# stm32l052k8t_dip.net
KiCad netlist of a schematic drawn in EAGLE
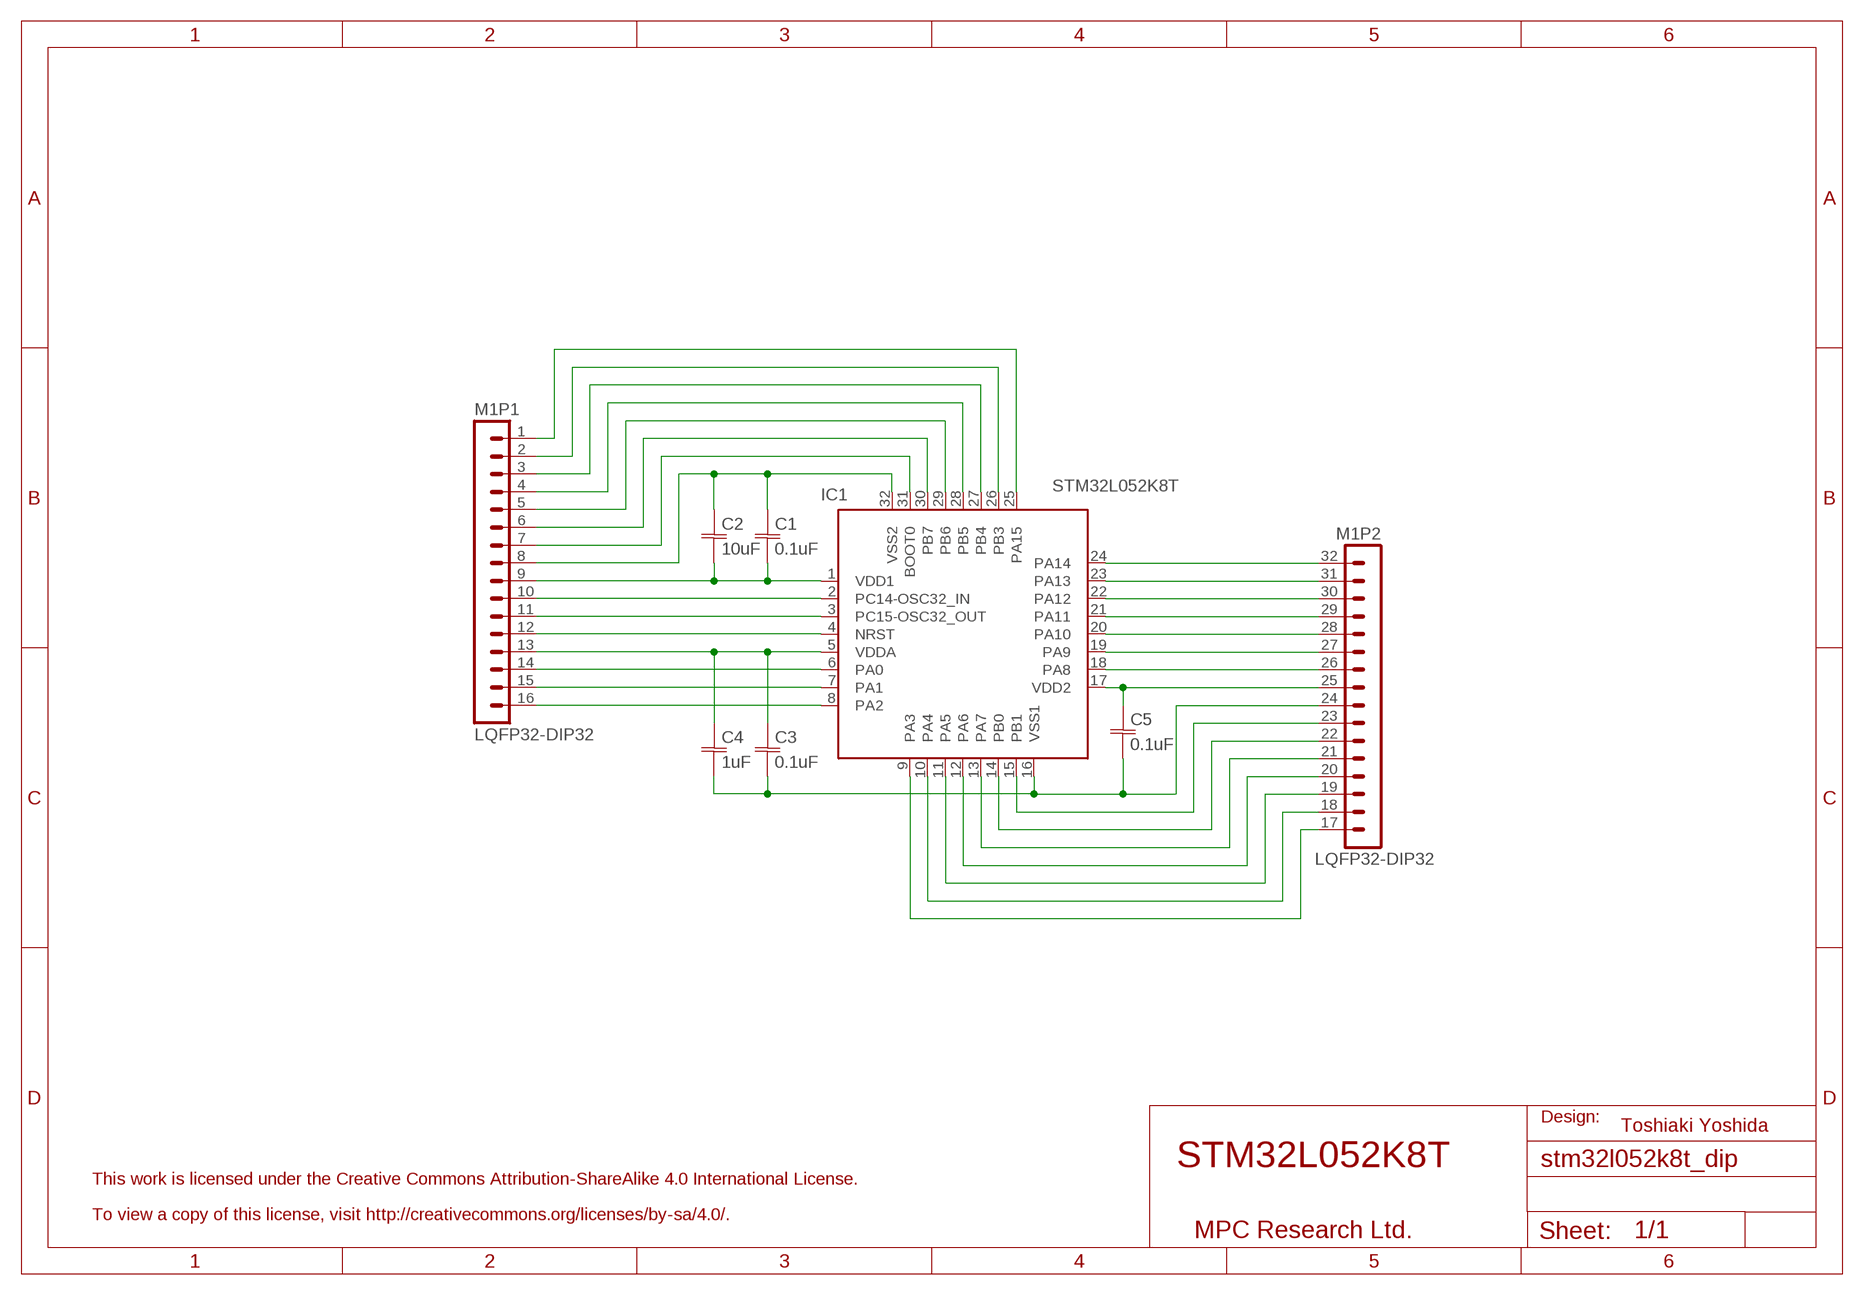
[diagram p0: schematic, sheet 1]

(export (version "E")
  (design (tool "Eeschema 10.0.6"))
  (components
    (comp (ref "C1")
      (value "0.1uF")
      (footprint "eagle-import:C0603")
      (libsource (lib "eagle-import") (part "C-JIS0603"))
    )
    (comp (ref "C2")
      (value "10uF")
      (footprint "eagle-import:C0603")
      (libsource (lib "eagle-import") (part "C-JIS0603"))
    )
    (comp (ref "C3")
      (value "0.1uF")
      (footprint "eagle-import:C0603")
      (libsource (lib "eagle-import") (part "C-JIS0603"))
    )
    (comp (ref "C4")
      (value "1uF")
      (footprint "eagle-import:C0603")
      (libsource (lib "eagle-import") (part "C-JIS0603"))
    )
    (comp (ref "C5")
      (value "0.1uF")
      (footprint "eagle-import:C0603")
      (libsource (lib "eagle-import") (part "C-JIS0603"))
    )
    (comp (ref "IC1")
      (value "STM32L052K8T")
      (footprint "eagle-import:LQFP-32")
      (libsource (lib "eagle-import") (part "STM32L052KT8"))
    )
    (comp (ref "M1")
      (value "LQFP32-DIP32")
      (footprint "eagle-import:LQFP32-DIP32")
      (libsource (lib "eagle-import") (part "LQFP32-DIP32"))
    )
  )
  (nets
    (net (code "1") (name "Net-(IC1-BOOT0)") (class "Default")
      (node (ref "IC1") (pin "31") (pinfunction "BOOT0_31") (pintype "input"))
      (node (ref "M1") (pin "7") (pinfunction "P7_7") (pintype "passive"))
    )
    (net (code "2") (name "Net-(IC1-NRST)") (class "Default")
      (node (ref "IC1") (pin "4") (pinfunction "NRST_4") (pintype "bidirectional"))
      (node (ref "M1") (pin "12") (pinfunction "P12_12") (pintype "passive"))
    )
    (net (code "3") (name "Net-(IC1-PA0)") (class "Default")
      (node (ref "IC1") (pin "6") (pinfunction "PA0_6") (pintype "bidirectional"))
      (node (ref "M1") (pin "14") (pinfunction "P14_14") (pintype "passive"))
    )
    (net (code "4") (name "Net-(IC1-PA1)") (class "Default")
      (node (ref "IC1") (pin "7") (pinfunction "PA1_7") (pintype "bidirectional"))
      (node (ref "M1") (pin "15") (pinfunction "P15_15") (pintype "passive"))
    )
    (net (code "5") (name "Net-(IC1-PA2)") (class "Default")
      (node (ref "IC1") (pin "8") (pinfunction "PA2_8") (pintype "bidirectional"))
      (node (ref "M1") (pin "16") (pinfunction "P16_16") (pintype "passive"))
    )
    (net (code "6") (name "Net-(IC1-PA3)") (class "Default")
      (node (ref "IC1") (pin "9") (pinfunction "PA3_9") (pintype "bidirectional"))
      (node (ref "M1") (pin "17") (pinfunction "P16_17") (pintype "passive"))
    )
    (net (code "7") (name "Net-(IC1-PA4)") (class "Default")
      (node (ref "IC1") (pin "10") (pinfunction "PA4_10") (pintype "bidirectional"))
      (node (ref "M1") (pin "18") (pinfunction "P15_18") (pintype "passive"))
    )
    (net (code "8") (name "Net-(IC1-PA5)") (class "Default")
      (node (ref "IC1") (pin "11") (pinfunction "PA5_11") (pintype "bidirectional"))
      (node (ref "M1") (pin "19") (pinfunction "P14_19") (pintype "passive"))
    )
    (net (code "9") (name "Net-(IC1-PA6)") (class "Default")
      (node (ref "IC1") (pin "12") (pinfunction "PA6_12") (pintype "bidirectional"))
      (node (ref "M1") (pin "20") (pinfunction "P13_20") (pintype "passive"))
    )
    (net (code "10") (name "Net-(IC1-PA7)") (class "Default")
      (node (ref "IC1") (pin "13") (pinfunction "PA7_13") (pintype "bidirectional"))
      (node (ref "M1") (pin "21") (pinfunction "P12_21") (pintype "passive"))
    )
    (net (code "11") (name "Net-(IC1-PA8)") (class "Default")
      (node (ref "IC1") (pin "18") (pinfunction "PA8_18") (pintype "bidirectional"))
      (node (ref "M1") (pin "26") (pinfunction "P7_26") (pintype "passive"))
    )
    (net (code "12") (name "Net-(IC1-PA9)") (class "Default")
      (node (ref "IC1") (pin "19") (pinfunction "PA9_19") (pintype "bidirectional"))
      (node (ref "M1") (pin "27") (pinfunction "P6_27") (pintype "passive"))
    )
    (net (code "13") (name "Net-(IC1-PA10)") (class "Default")
      (node (ref "IC1") (pin "20") (pinfunction "PA10_20") (pintype "bidirectional"))
      (node (ref "M1") (pin "28") (pinfunction "P5_28") (pintype "passive"))
    )
    (net (code "14") (name "Net-(IC1-PA11)") (class "Default")
      (node (ref "IC1") (pin "21") (pinfunction "PA11_21") (pintype "bidirectional"))
      (node (ref "M1") (pin "29") (pinfunction "P4_29") (pintype "passive"))
    )
    (net (code "15") (name "Net-(IC1-PA12)") (class "Default")
      (node (ref "IC1") (pin "22") (pinfunction "PA12_22") (pintype "bidirectional"))
      (node (ref "M1") (pin "30") (pinfunction "P3_30") (pintype "passive"))
    )
    (net (code "16") (name "Net-(IC1-PA13)") (class "Default")
      (node (ref "IC1") (pin "23") (pinfunction "PA13_23") (pintype "bidirectional"))
      (node (ref "M1") (pin "31") (pinfunction "P2_31") (pintype "passive"))
    )
    (net (code "17") (name "Net-(IC1-PA14)") (class "Default")
      (node (ref "IC1") (pin "24") (pinfunction "PA14_24") (pintype "bidirectional"))
      (node (ref "M1") (pin "32") (pinfunction "P1_32") (pintype "passive"))
    )
    (net (code "18") (name "Net-(IC1-PA15)") (class "Default")
      (node (ref "IC1") (pin "25") (pinfunction "PA15_25") (pintype "bidirectional"))
      (node (ref "M1") (pin "1") (pinfunction "P1_1") (pintype "passive"))
    )
    (net (code "19") (name "Net-(IC1-PB0)") (class "Default")
      (node (ref "IC1") (pin "14") (pinfunction "PB0_14") (pintype "bidirectional"))
      (node (ref "M1") (pin "22") (pinfunction "P11_22") (pintype "passive"))
    )
    (net (code "20") (name "Net-(IC1-PB1)") (class "Default")
      (node (ref "IC1") (pin "15") (pinfunction "PB1_15") (pintype "bidirectional"))
      (node (ref "M1") (pin "23") (pinfunction "P10_23") (pintype "passive"))
    )
    (net (code "21") (name "Net-(IC1-PB3)") (class "Default")
      (node (ref "IC1") (pin "26") (pinfunction "PB3_26") (pintype "bidirectional"))
      (node (ref "M1") (pin "2") (pinfunction "P2_2") (pintype "passive"))
    )
    (net (code "22") (name "Net-(IC1-PB4)") (class "Default")
      (node (ref "IC1") (pin "27") (pinfunction "PB4_27") (pintype "bidirectional"))
      (node (ref "M1") (pin "3") (pinfunction "P3_3") (pintype "passive"))
    )
    (net (code "23") (name "Net-(IC1-PB5)") (class "Default")
      (node (ref "IC1") (pin "28") (pinfunction "PB5_28") (pintype "bidirectional"))
      (node (ref "M1") (pin "4") (pinfunction "P4_4") (pintype "passive"))
    )
    (net (code "24") (name "Net-(IC1-PB6)") (class "Default")
      (node (ref "IC1") (pin "29") (pinfunction "PB6_29") (pintype "bidirectional"))
      (node (ref "M1") (pin "5") (pinfunction "P5_5") (pintype "passive"))
    )
    (net (code "25") (name "Net-(IC1-PB7)") (class "Default")
      (node (ref "IC1") (pin "30") (pinfunction "PB7_30") (pintype "bidirectional"))
      (node (ref "M1") (pin "6") (pinfunction "P6_6") (pintype "passive"))
    )
    (net (code "26") (name "Net-(IC1-PC14-OSC32_IN)") (class "Default")
      (node (ref "IC1") (pin "2") (pinfunction "PC14-OSC32_IN_2") (pintype "bidirectional"))
      (node (ref "M1") (pin "10") (pinfunction "P10_10") (pintype "passive"))
    )
    (net (code "27") (name "Net-(IC1-PC15-OSC32_OUT)") (class "Default")
      (node (ref "IC1") (pin "3") (pinfunction "PC15-OSC32_OUT_3") (pintype "bidirectional"))
      (node (ref "M1") (pin "11") (pinfunction "P11_11") (pintype "passive"))
    )
    (net (code "28") (name "Net-(IC1-VDD1)") (class "Default")
      (node (ref "C1") (pin "2") (pinfunction "2_2") (pintype "passive"))
      (node (ref "C2") (pin "2") (pinfunction "2_2") (pintype "passive"))
      (node (ref "IC1") (pin "1") (pinfunction "VDD1_1") (pintype "power_in"))
      (node (ref "M1") (pin "9") (pinfunction "P9_9") (pintype "passive"))
    )
    (net (code "29") (name "Net-(IC1-VDD2)") (class "Default")
      (node (ref "C5") (pin "1") (pinfunction "1_1") (pintype "passive"))
      (node (ref "IC1") (pin "17") (pinfunction "VDD2_17") (pintype "bidirectional"))
      (node (ref "M1") (pin "25") (pinfunction "P8_25") (pintype "passive"))
    )
    (net (code "30") (name "Net-(IC1-VDDA)") (class "Default")
      (node (ref "C3") (pin "1") (pinfunction "1_1") (pintype "passive"))
      (node (ref "C4") (pin "1") (pinfunction "1_1") (pintype "passive"))
      (node (ref "IC1") (pin "5") (pinfunction "VDDA_5") (pintype "power_in"))
      (node (ref "M1") (pin "13") (pinfunction "P13_13") (pintype "passive"))
    )
    (net (code "31") (name "Net-(IC1-VSS1)") (class "Default")
      (node (ref "C3") (pin "2") (pinfunction "2_2") (pintype "passive"))
      (node (ref "C4") (pin "2") (pinfunction "2_2") (pintype "passive"))
      (node (ref "C5") (pin "2") (pinfunction "2_2") (pintype "passive"))
      (node (ref "IC1") (pin "16") (pinfunction "VSS1_16") (pintype "power_in"))
      (node (ref "M1") (pin "24") (pinfunction "P9_24") (pintype "passive"))
    )
    (net (code "32") (name "Net-(IC1-VSS2)") (class "Default")
      (node (ref "C1") (pin "1") (pinfunction "1_1") (pintype "passive"))
      (node (ref "C2") (pin "1") (pinfunction "1_1") (pintype "passive"))
      (node (ref "IC1") (pin "32") (pinfunction "VSS2_32") (pintype "power_in"))
      (node (ref "M1") (pin "8") (pinfunction "P8_8") (pintype "passive"))
    )
  )
)
